# Schmitz_VCO.net
KiCad netlist of a schematic drawn in EAGLE
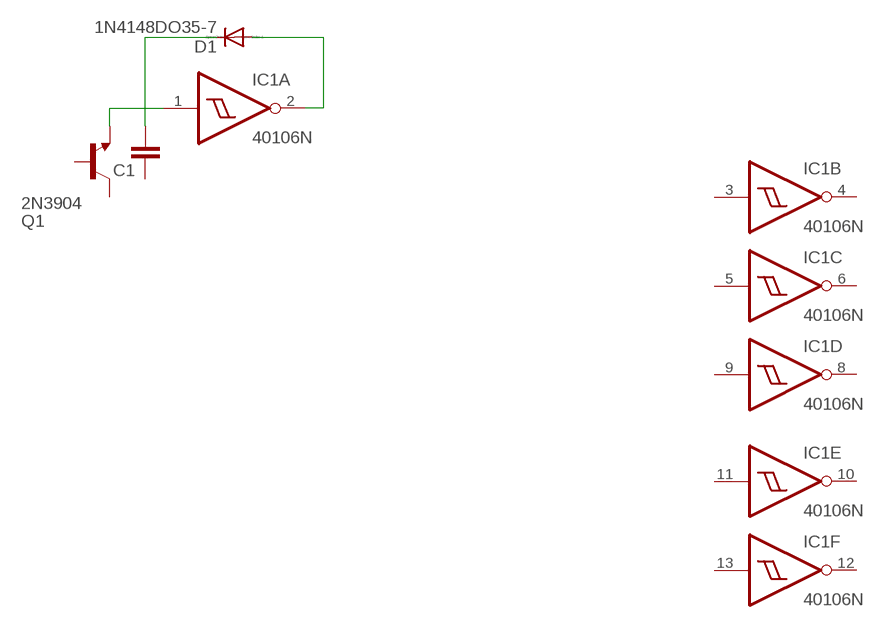
[diagram p0: schematic, sheet 1]

(export (version "E")
  (design (tool "Eeschema 10.0.6"))
  (components
    (comp (ref "C1")
      (value "C-EU075-032X103")
      (footprint "eagle-import:C075-032X103")
      (libsource (lib "eagle-import") (part "C-EU075-032X103"))
    )
    (comp (ref "D1")
      (value "1N4148DO35-7")
      (footprint "eagle-import:DO35-7")
      (libsource (lib "eagle-import") (part "1N4148DO35-7"))
    )
    (comp (ref "IC1")
      (value "40106N")
      (footprint "eagle-import:DIL14")
      (libsource (lib "eagle-import") (part "40106N"))
    )
    (comp (ref "Q1")
      (value "2N3904")
      (footprint "eagle-import:TO92")
      (libsource (lib "eagle-import") (part "2N3904"))
    )
  )
  (nets
    (net (code "1") (name "Net-(IC1A-I)") (class "Default")
      (node (ref "C1") (pin "2") (pinfunction "2_2") (pintype "passive"))
      (node (ref "D1") (pin "C") (pinfunction "C_C") (pintype "passive"))
      (node (ref "IC1") (pin "1") (pinfunction "I_1") (pintype "input"))
      (node (ref "Q1") (pin "3") (pinfunction "E_3") (pintype "passive"))
    )
    (net (code "2") (name "Net-(IC1A-O)") (class "Default")
      (node (ref "D1") (pin "A") (pinfunction "A_A") (pintype "passive"))
      (node (ref "IC1") (pin "2") (pinfunction "O_2") (pintype "output"))
    )
    (net (code "3") (name "unconnected-(C1-Pad1)") (class "Default")
      (node (ref "C1") (pin "1") (pinfunction "1_1") (pintype "passive"))
    )
    (net (code "4") (name "unconnected-(IC1B-I-Pad3)") (class "Default")
      (node (ref "IC1") (pin "3") (pinfunction "I_3") (pintype "input"))
    )
    (net (code "5") (name "unconnected-(IC1B-O-Pad4)") (class "Default")
      (node (ref "IC1") (pin "4") (pinfunction "O_4") (pintype "output"))
    )
    (net (code "6") (name "unconnected-(IC1C-I-Pad5)") (class "Default")
      (node (ref "IC1") (pin "5") (pinfunction "I_5") (pintype "input"))
    )
    (net (code "7") (name "unconnected-(IC1C-O-Pad6)") (class "Default")
      (node (ref "IC1") (pin "6") (pinfunction "O_6") (pintype "output"))
    )
    (net (code "8") (name "unconnected-(IC1D-I-Pad9)") (class "Default")
      (node (ref "IC1") (pin "9") (pinfunction "I_9") (pintype "input"))
    )
    (net (code "9") (name "unconnected-(IC1D-O-Pad8)") (class "Default")
      (node (ref "IC1") (pin "8") (pinfunction "O_8") (pintype "output"))
    )
    (net (code "10") (name "unconnected-(IC1E-I-Pad11)") (class "Default")
      (node (ref "IC1") (pin "11") (pinfunction "I_11") (pintype "input"))
    )
    (net (code "11") (name "unconnected-(IC1E-O-Pad10)") (class "Default")
      (node (ref "IC1") (pin "10") (pinfunction "O_10") (pintype "output"))
    )
    (net (code "12") (name "unconnected-(IC1F-I-Pad13)") (class "Default")
      (node (ref "IC1") (pin "13") (pinfunction "I_13") (pintype "input"))
    )
    (net (code "13") (name "unconnected-(IC1F-O-Pad12)") (class "Default")
      (node (ref "IC1") (pin "12") (pinfunction "O_12") (pintype "output"))
    )
    (net (code "14") (name "unconnected-(Q1-B-Pad2)") (class "Default")
      (node (ref "Q1") (pin "2") (pinfunction "B_2") (pintype "passive"))
    )
    (net (code "15") (name "unconnected-(Q1-C-Pad1)") (class "Default")
      (node (ref "Q1") (pin "1") (pinfunction "C_1") (pintype "passive"))
    )
  )
)
